# Auxiliary_Horn.net
KiCad netlist of a schematic drawn in Altium Designer
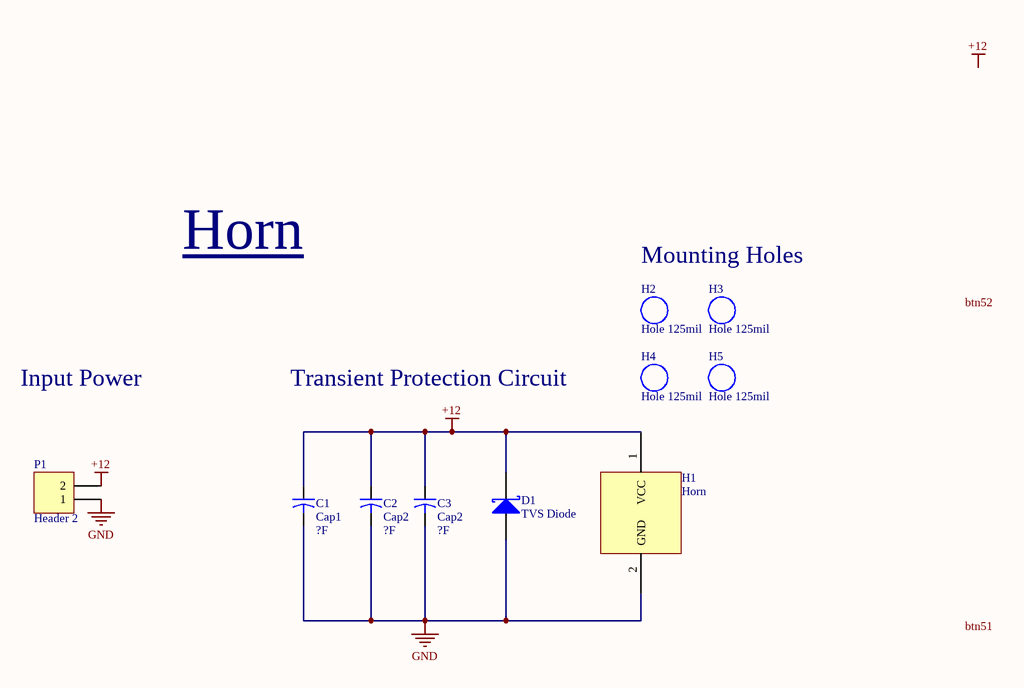
[diagram p0: Auxiliary_Horn.SchDoc]

(export (version "E")
  (design (tool "Eeschema 10.0.6"))
  (components
    (comp (ref "C1")
      (value "Cap1")
      (footprint "CAPR5-4X5")
      (description "Capacitor")
      (fields (field (name "ALTIUM_VALUE") "?F") (field (name "PUBLISHER") "Altium Limited"))
      (libsource (lib "Miscellaneous Devices") (part "Cap2"))
    )
    (comp (ref "C2")
      (value "Cap2")
      (footprint "CAPR5-4X5")
      (description "Capacitor")
      (fields (field (name "ALTIUM_VALUE") "?F") (field (name "PUBLISHER") "Altium Limited"))
      (libsource (lib "Miscellaneous Devices") (part "Cap2"))
    )
    (comp (ref "C3")
      (value "Cap2")
      (footprint "CAPR5-4X5")
      (description "Capacitor")
      (fields (field (name "ALTIUM_VALUE") "?F") (field (name "PUBLISHER") "Altium Limited"))
      (libsource (lib "Miscellaneous Devices") (part "Cap2"))
    )
    (comp (ref "D1")
      (value "TVS Diode")
      (footprint "DO-204AL")
      (description "Schottky Rectifier")
      (fields (field (name "PUBLISHER") "Altium Limited"))
      (libsource (lib "Miscellaneous Devices") (part "Diode 11DQ03"))
    )
    (comp (ref "H1") (value "Horn") (footprint "Horn_Pads") (libsource (lib "Horn") (part "hornPads")))
    (comp (ref "H2")
      (value "Hole 125mil")
      (footprint "Hole 125mil")
      (libsource (lib "ECE LIB new") (part "Hole 125mil"))
    )
    (comp (ref "H3")
      (value "Hole 125mil")
      (footprint "Hole 125mil")
      (libsource (lib "ECE LIB new") (part "Hole 125mil"))
    )
    (comp (ref "H4")
      (value "Hole 125mil")
      (footprint "Hole 125mil")
      (libsource (lib "ECE LIB new") (part "Hole 125mil"))
    )
    (comp (ref "H5")
      (value "Hole 125mil")
      (footprint "Hole 125mil")
      (libsource (lib "ECE LIB new") (part "Hole 125mil"))
    )
    (comp (ref "P1")
      (value "Header 2")
      (footprint "HDR1X2")
      (description "Header, 2-Pin")
      (fields (field (name "PUBLISHER") "Altium Limited"))
      (libsource (lib "Miscellaneous Connectors") (part "Header 2"))
    )
  )
  (nets
    (net (code "1") (name "+12") (class "Default")
      (node (ref "C1") (pin "1") (pinfunction "1_1") (pintype "passive"))
      (node (ref "C2") (pin "1") (pinfunction "1_1") (pintype "passive"))
      (node (ref "C3") (pin "1") (pinfunction "1_1") (pintype "passive"))
      (node (ref "D1") (pin "2") (pinfunction "K_2") (pintype "passive"))
      (node (ref "H1") (pin "1") (pinfunction "VCC_1") (pintype "passive"))
      (node (ref "P1") (pin "2") (pinfunction "2_2") (pintype "passive"))
    )
    (net (code "4") (name "GND") (class "Default")
      (node (ref "C1") (pin "2") (pinfunction "2_2") (pintype "passive"))
      (node (ref "C2") (pin "2") (pinfunction "2_2") (pintype "passive"))
      (node (ref "C3") (pin "2") (pinfunction "2_2") (pintype "passive"))
      (node (ref "D1") (pin "1") (pinfunction "A_1") (pintype "passive"))
      (node (ref "H1") (pin "2") (pinfunction "GND_2") (pintype "passive"))
      (node (ref "P1") (pin "1") (pinfunction "1_1") (pintype "passive"))
    )
  )
)
